# PIC32_Subsystem.net
KiCad netlist of a schematic drawn in Altium Designer
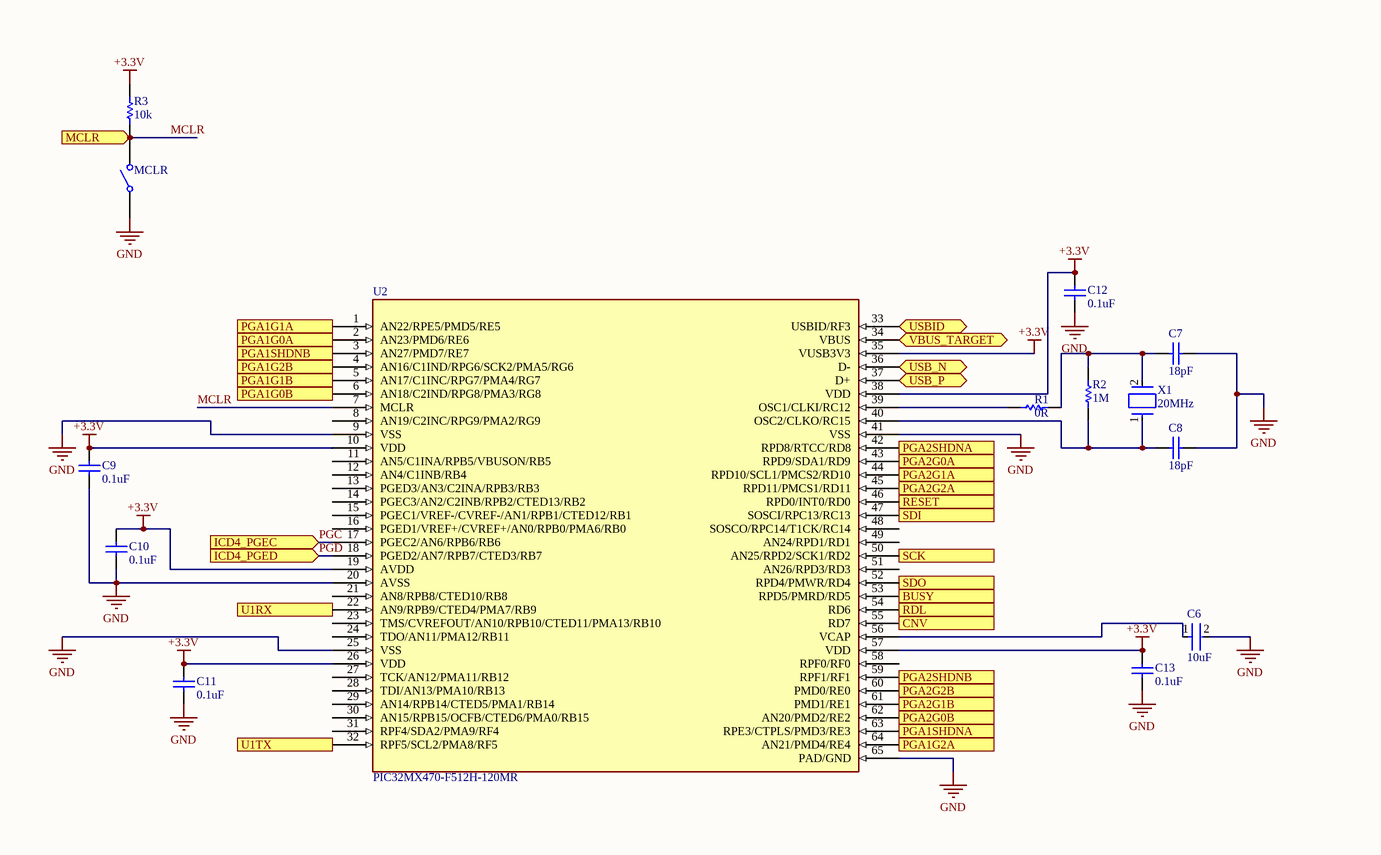
[diagram p0: PIC32_Subsystem.SchDoc, left]

(export (version "E")
  (design (tool "Eeschema 10.0.6"))
  (components
    (comp (ref "C6")
      (value "10uF")
      (footprint "FP-GRM188-0_1-e0_2_0_55-IPC_A")
      (fields (field (name "VOLTAGE") "6.3V") (field (name "TOLERANCE") "20%"))
      (libsource (lib "Altium Content Vault") (part "02cd4be3c70576c341d710602a673aa"))
    )
    (comp (ref "C7")
      (value "18pF")
      (footprint "CAPC1005X55X25LL05T10")
      (description "GRM1555C1H180GA01D")
      (fields (field (name "MANUFACTURER") "Murata"))
      (libsource (lib "Altium Content Vault") (part "CAP"))
    )
    (comp (ref "C8")
      (value "18pF")
      (footprint "CAPC1005X55X25LL05T10")
      (description "GRM1555C1H180GA01D")
      (fields (field (name "MANUFACTURER") "Murata"))
      (libsource (lib "Altium Content Vault") (part "CAP"))
    )
    (comp (ref "C9")
      (value "0.1uF")
      (footprint "CAPC1050X55X23ML05T13")
      (fields (field (name "MANUFACTURER") "Samsung Electro-Mechanics"))
      (libsource (lib "Altium Content Vault") (part "CAP-NP-2"))
    )
    (comp (ref "C10")
      (value "0.1uF")
      (footprint "CAPC1050X55X23ML05T13")
      (fields (field (name "MANUFACTURER") "Samsung Electro-Mechanics"))
      (libsource (lib "Altium Content Vault") (part "CAP-NP-2"))
    )
    (comp (ref "C11")
      (value "0.1uF")
      (footprint "CAPC1050X55X23ML05T13")
      (fields (field (name "MANUFACTURER") "Samsung Electro-Mechanics"))
      (libsource (lib "Altium Content Vault") (part "CAP-NP-2"))
    )
    (comp (ref "C12")
      (value "0.1uF")
      (footprint "CAPC1050X55X23ML05T13")
      (fields (field (name "MANUFACTURER") "Samsung Electro-Mechanics"))
      (libsource (lib "Altium Content Vault") (part "CAP-NP-2"))
    )
    (comp (ref "C13")
      (value "0.1uF")
      (footprint "CAPC1050X55X23ML05T13")
      (fields (field (name "MANUFACTURER") "Samsung Electro-Mechanics"))
      (libsource (lib "Altium Content Vault") (part "CAP-NP-2"))
    )
    (comp (ref "MCLR")
      (value "434121043816")
      (footprint "434121043816")
      (description "WS-TASV SMD Tact Switch 6.0X3.5 mm")
      (fields (field (name "MANUFACTURER") "Wuerth Elektronik"))
      (libsource (lib "Altium Content Vault") (part "WE-TACT-SW-2"))
    )
    (comp (ref "R1")
      (value "0R")
      (footprint "RESC1005X40X25NL05T10")
      (description "RC0402JR-070RL")
      (fields (field (name "MANUFACTURER") "Yageo / Phycomp"))
      (libsource (lib "Altium Content Vault") (part "RES"))
    )
    (comp (ref "R2")
      (value "1M")
      (footprint "RESC1005X40X25LL05T05")
      (fields
        (field (name "PARTNUMBER") "ERJ-2RKF1004X")
        (field (name "TOLERANCE") "1%")
        (field (name "MANUFACTURER") "Basic Passives")
      )
      (libsource (lib "Altium Content Vault") (part "RES-2"))
    )
    (comp (ref "R3")
      (value "10k")
      (footprint "RESC1005X40X25LL05T05")
      (fields (field (name "TOLERANCE") "1%") (field (name "MANUFACTURER") "Panasonic"))
      (libsource (lib "Altium Content Vault") (part "RES-2"))
    )
    (comp (ref "U2")
      (value "PIC32MX470-F512H-120MR")
      (footprint "QFN50P900X900X100-65N")
      (libsource (lib "PIC32MX470-F512H-120MR") (part "PIC32MX470-F512H-120MR"))
    )
    (comp (ref "X1")
      (value "20MHz")
      (footprint "FP-ABM7-MFG")
      (description "Crystal 20MHz ±20ppm 18pF SMD-2 6mm x 3.5mm\r\nABM7-20.000MHZ-D2Y-T")
      (fields (field (name "TOLERANCE") "20ppm"))
      (libsource (lib "Altium Content Vault") (part "c23a69dc6c9e2f18f2079038eb95dd1"))
    )
  )
  (nets
    (net (code "1") (name "+3.3V") (class "Default")
      (node (ref "C10") (pin "2") (pinfunction "2_2") (pintype "passive"))
      (node (ref "C11") (pin "2") (pinfunction "2_2") (pintype "passive"))
      (node (ref "C12") (pin "2") (pinfunction "2_2") (pintype "passive"))
      (node (ref "C13") (pin "2") (pinfunction "2_2") (pintype "passive"))
      (node (ref "C9") (pin "2") (pinfunction "2_2") (pintype "passive"))
      (node (ref "R3") (pin "2") (pinfunction "2_2") (pintype "passive"))
      (node (ref "U2") (pin "10") (pinfunction "VDD_10") (pintype "input"))
      (node (ref "U2") (pin "19") (pinfunction "AVDD_19") (pintype "input"))
      (node (ref "U2") (pin "26") (pinfunction "VDD_26") (pintype "input"))
      (node (ref "U2") (pin "35") (pinfunction "VUSB3V3_35") (pintype "input"))
      (node (ref "U2") (pin "38") (pinfunction "VDD_38") (pintype "input"))
      (node (ref "U2") (pin "57") (pinfunction "VDD_57") (pintype "input"))
    )
    (net (code "2") (name "/BUSY") (class "Default")
      (node (ref "U2") (pin "53") (pinfunction "RPD5/PMRD/RD5_53") (pintype "input"))
    )
    (net (code "3") (name "/CNV") (class "Default")
      (node (ref "U2") (pin "55") (pinfunction "RD7_55") (pintype "input"))
    )
    (net (code "4") (name "/MCLR") (class "Default")
      (node (ref "MCLR") (pin "2") (pinfunction "2_2") (pintype "passive"))
      (node (ref "R3") (pin "1") (pinfunction "1_1") (pintype "passive"))
      (node (ref "U2") (pin "7") (pinfunction "MCLR_7") (pintype "input"))
    )
    (net (code "5") (name "/PGA1G0A") (class "Default")
      (node (ref "U2") (pin "2") (pinfunction "AN23/PMD6/RE6_2") (pintype "input"))
    )
    (net (code "6") (name "/PGA1G0B") (class "Default")
      (node (ref "U2") (pin "6") (pinfunction "AN18/C2IND/RPG8/PMA3/RG8_6") (pintype "input"))
    )
    (net (code "7") (name "/PGA1G1A") (class "Default")
      (node (ref "U2") (pin "1") (pinfunction "AN22/RPE5/PMD5/RE5_1") (pintype "input"))
    )
    (net (code "8") (name "/PGA1G1B") (class "Default")
      (node (ref "U2") (pin "5") (pinfunction "AN17/C1INC/RPG7/PMA4/RG7_5") (pintype "input"))
    )
    (net (code "9") (name "/PGA1G2A") (class "Default")
      (node (ref "U2") (pin "64") (pinfunction "AN21/PMD4/RE4_64") (pintype "input"))
    )
    (net (code "10") (name "/PGA1G2B") (class "Default")
      (node (ref "U2") (pin "4") (pinfunction "AN16/C1IND/RPG6/SCK2/PMA5/RG6_4") (pintype "input"))
    )
    (net (code "11") (name "/PGA1SHDNA") (class "Default")
      (node (ref "U2") (pin "63") (pinfunction "RPE3/CTPLS/PMD3/RE3_63") (pintype "input"))
    )
    (net (code "12") (name "/PGA1SHDNB") (class "Default")
      (node (ref "U2") (pin "3") (pinfunction "AN27/PMD7/RE7_3") (pintype "input"))
    )
    (net (code "13") (name "/PGA2G0A") (class "Default")
      (node (ref "U2") (pin "43") (pinfunction "RPD9/SDA1/RD9_43") (pintype "input"))
    )
    (net (code "14") (name "/PGA2G0B") (class "Default")
      (node (ref "U2") (pin "62") (pinfunction "AN20/PMD2/RE2_62") (pintype "input"))
    )
    (net (code "15") (name "/PGA2G1A") (class "Default")
      (node (ref "U2") (pin "44") (pinfunction "RPD10/SCL1/PMCS2/RD10_44") (pintype "input"))
    )
    (net (code "16") (name "/PGA2G1B") (class "Default")
      (node (ref "U2") (pin "61") (pinfunction "PMD1/RE1_61") (pintype "input"))
    )
    (net (code "17") (name "/PGA2G2A") (class "Default")
      (node (ref "U2") (pin "45") (pinfunction "RPD11/PMCS1/RD11_45") (pintype "input"))
    )
    (net (code "18") (name "/PGA2G2B") (class "Default")
      (node (ref "U2") (pin "60") (pinfunction "PMD0/RE0_60") (pintype "input"))
    )
    (net (code "19") (name "/PGA2SHDNA") (class "Default")
      (node (ref "U2") (pin "42") (pinfunction "RPD8/RTCC/RD8_42") (pintype "input"))
    )
    (net (code "20") (name "/PGA2SHDNB") (class "Default")
      (node (ref "U2") (pin "59") (pinfunction "RPF1/RF1_59") (pintype "input"))
    )
    (net (code "21") (name "/PGC") (class "Default")
      (node (ref "U2") (pin "17") (pinfunction "PGEC2/AN6/RPB6/RB6_17") (pintype "input"))
    )
    (net (code "22") (name "/PGD") (class "Default")
      (node (ref "U2") (pin "18") (pinfunction "PGED2/AN7/RPB7/CTED3/RB7_18") (pintype "input"))
    )
    (net (code "23") (name "/RDL") (class "Default")
      (node (ref "U2") (pin "54") (pinfunction "RD6_54") (pintype "input"))
    )
    (net (code "24") (name "/RESET") (class "Default")
      (node (ref "U2") (pin "46") (pinfunction "RPD0/INT0/RD0_46") (pintype "input"))
    )
    (net (code "25") (name "/SCK") (class "Default")
      (node (ref "U2") (pin "50") (pinfunction "AN25/RPD2/SCK1/RD2_50") (pintype "input"))
    )
    (net (code "26") (name "/SDI") (class "Default")
      (node (ref "U2") (pin "47") (pinfunction "SOSCI/RPC13/RC13_47") (pintype "input"))
    )
    (net (code "27") (name "/SDO") (class "Default")
      (node (ref "U2") (pin "52") (pinfunction "RPD4/PMWR/RD4_52") (pintype "input"))
    )
    (net (code "28") (name "/U1RX") (class "Default")
      (node (ref "U2") (pin "22") (pinfunction "AN9/RPB9/CTED4/PMA7/RB9_22") (pintype "input"))
    )
    (net (code "29") (name "/U1TX") (class "Default")
      (node (ref "U2") (pin "32") (pinfunction "RPF5/SCL2/PMA8/RF5_32") (pintype "input"))
    )
    (net (code "30") (name "/USBID") (class "Default")
      (node (ref "U2") (pin "33") (pinfunction "USBID/RF3_33") (pintype "input"))
    )
    (net (code "31") (name "/USB_N") (class "Default")
      (node (ref "U2") (pin "36") (pinfunction "D-_36") (pintype "input"))
    )
    (net (code "32") (name "/USB_P") (class "Default")
      (node (ref "U2") (pin "37") (pinfunction "D+_37") (pintype "input"))
    )
    (net (code "33") (name "/VBUS_TARGET") (class "Default")
      (node (ref "U2") (pin "34") (pinfunction "VBUS_34") (pintype "input"))
    )
    (net (code "34") (name "GND") (class "Default")
      (node (ref "C10") (pin "1") (pinfunction "1_1") (pintype "passive"))
      (node (ref "C11") (pin "1") (pinfunction "1_1") (pintype "passive"))
      (node (ref "C12") (pin "1") (pinfunction "1_1") (pintype "passive"))
      (node (ref "C13") (pin "1") (pinfunction "1_1") (pintype "passive"))
      (node (ref "C6") (pin "2") (pinfunction "2_2") (pintype "passive"))
      (node (ref "C7") (pin "2") (pinfunction "2_2") (pintype "passive"))
      (node (ref "C8") (pin "2") (pinfunction "2_2") (pintype "passive"))
      (node (ref "C9") (pin "1") (pinfunction "1_1") (pintype "passive"))
      (node (ref "MCLR") (pin "1") (pinfunction "1_1") (pintype "passive"))
      (node (ref "U2") (pin "20") (pinfunction "AVSS_20") (pintype "input"))
      (node (ref "U2") (pin "25") (pinfunction "VSS_25") (pintype "input"))
      (node (ref "U2") (pin "41") (pinfunction "VSS_41") (pintype "input"))
      (node (ref "U2") (pin "65") (pinfunction "PAD/GND_65") (pintype "input"))
      (node (ref "U2") (pin "9") (pinfunction "VSS_9") (pintype "input"))
    )
    (net (code "35") (name "Net-(C7-Pad1)") (class "Default")
      (node (ref "C7") (pin "1") (pinfunction "1_1") (pintype "passive"))
      (node (ref "R1") (pin "2") (pinfunction "2_2") (pintype "passive"))
      (node (ref "R2") (pin "2") (pinfunction "2_2") (pintype "passive"))
      (node (ref "X1") (pin "2") (pinfunction "2_2") (pintype "passive"))
    )
    (net (code "36") (name "Net-(U2-OSC1{slash}CLKI{slash}RC12)") (class "Default")
      (node (ref "R1") (pin "1") (pinfunction "1_1") (pintype "passive"))
      (node (ref "U2") (pin "39") (pinfunction "OSC1/CLKI/RC12_39") (pintype "input"))
    )
    (net (code "37") (name "Net-(U2-OSC2{slash}CLKO{slash}RC15)") (class "Default")
      (node (ref "C8") (pin "1") (pinfunction "1_1") (pintype "passive"))
      (node (ref "R2") (pin "1") (pinfunction "1_1") (pintype "passive"))
      (node (ref "U2") (pin "40") (pinfunction "OSC2/CLKO/RC15_40") (pintype "input"))
      (node (ref "X1") (pin "1") (pinfunction "1_1") (pintype "passive"))
    )
    (net (code "38") (name "Net-(U2-VCAP)") (class "Default")
      (node (ref "C6") (pin "1") (pinfunction "1_1") (pintype "passive"))
      (node (ref "U2") (pin "56") (pinfunction "VCAP_56") (pintype "input"))
    )
    (net (code "39") (name "unconnected-(U2-AN4{slash}C1INB{slash}RB4-Pad12)") (class "Default")
      (node (ref "U2") (pin "12") (pinfunction "AN4/C1INB/RB4_12") (pintype "input"))
    )
    (net (code "40") (name "unconnected-(U2-AN5{slash}C1INA{slash}RPB5{slash}VBUSON{slash}RB5-Pad11)") (class "Default")
      (node (ref "U2") (pin "11") (pinfunction "AN5/C1INA/RPB5/VBUSON/RB5_11") (pintype "input"))
    )
    (net (code "41") (name "unconnected-(U2-AN8{slash}RPB8{slash}CTED10{slash}RB8-Pad21)") (class "Default")
      (node (ref "U2") (pin "21") (pinfunction "AN8/RPB8/CTED10/RB8_21") (pintype "input"))
    )
    (net (code "42") (name "unconnected-(U2-AN14{slash}RPB14{slash}CTED5{slash}PMA1{slash}RB14-Pad29)") (class "Default")
      (node (ref "U2") (pin "29") (pinfunction "AN14/RPB14/CTED5/PMA1/RB14_29") (pintype "input"))
    )
    (net (code "43") (name "unconnected-(U2-AN15{slash}RPB15{slash}OCFB{slash}CTED6{slash}PMA0{slash}RB15-Pad30)") (class "Default")
      (node (ref "U2") (pin "30") (pinfunction "AN15/RPB15/OCFB/CTED6/PMA0/RB15_30") (pintype "input"))
    )
    (net (code "44") (name "unconnected-(U2-AN19{slash}C2INC{slash}RPG9{slash}PMA2{slash}RG9-Pad8)") (class "Default")
      (node (ref "U2") (pin "8") (pinfunction "AN19/C2INC/RPG9/PMA2/RG9_8") (pintype "input"))
    )
    (net (code "45") (name "unconnected-(U2-AN24{slash}RPD1{slash}RD1-Pad49)") (class "Default")
      (node (ref "U2") (pin "49") (pinfunction "AN24/RPD1/RD1_49") (pintype "input"))
    )
    (net (code "46") (name "unconnected-(U2-AN26{slash}RPD3{slash}RD3-Pad51)") (class "Default")
      (node (ref "U2") (pin "51") (pinfunction "AN26/RPD3/RD3_51") (pintype "input"))
    )
    (net (code "47") (name "unconnected-(U2-PGEC1{slash}VREF-{slash}CVREF-{slash}AN1{slash}RPB1{slash}CTED12{slash}RB1-Pad15)") (class "Default")
      (node (ref "U2") (pin "15") (pinfunction "PGEC1/VREF-/CVREF-/AN1/RPB1/CTED12/RB1_15") (pintype "input"))
    )
    (net (code "48") (name "unconnected-(U2-PGEC3{slash}AN2{slash}C2INB{slash}RPB2{slash}CTED13{slash}RB2-Pad14)") (class "Default")
      (node (ref "U2") (pin "14") (pinfunction "PGEC3/AN2/C2INB/RPB2/CTED13/RB2_14") (pintype "input"))
    )
    (net (code "49") (name "unconnected-(U2-PGED1{slash}VREF+{slash}CVREF+{slash}AN0{slash}RPB0{slash}PMA6{slash}RB0-Pad16)") (class "Default")
      (node (ref "U2") (pin "16") (pinfunction "PGED1/VREF+/CVREF+/AN0/RPB0/PMA6/RB0_16") (pintype "input"))
    )
    (net (code "50") (name "unconnected-(U2-PGED3{slash}AN3{slash}C2INA{slash}RPB3{slash}RB3-Pad13)") (class "Default")
      (node (ref "U2") (pin "13") (pinfunction "PGED3/AN3/C2INA/RPB3/RB3_13") (pintype "input"))
    )
    (net (code "51") (name "unconnected-(U2-RPF0{slash}RF0-Pad58)") (class "Default")
      (node (ref "U2") (pin "58") (pinfunction "RPF0/RF0_58") (pintype "input"))
    )
    (net (code "52") (name "unconnected-(U2-RPF4{slash}SDA2{slash}PMA9{slash}RF4-Pad31)") (class "Default")
      (node (ref "U2") (pin "31") (pinfunction "RPF4/SDA2/PMA9/RF4_31") (pintype "input"))
    )
    (net (code "53") (name "unconnected-(U2-SOSCO{slash}RPC14{slash}T1CK{slash}RC14-Pad48)") (class "Default")
      (node (ref "U2") (pin "48") (pinfunction "SOSCO/RPC14/T1CK/RC14_48") (pintype "input"))
    )
    (net (code "54") (name "unconnected-(U2-TCK{slash}AN12{slash}PMA11{slash}RB12-Pad27)") (class "Default")
      (node (ref "U2") (pin "27") (pinfunction "TCK/AN12/PMA11/RB12_27") (pintype "input"))
    )
    (net (code "55") (name "unconnected-(U2-TDI{slash}AN13{slash}PMA10{slash}RB13-Pad28)") (class "Default")
      (node (ref "U2") (pin "28") (pinfunction "TDI/AN13/PMA10/RB13_28") (pintype "input"))
    )
    (net (code "56") (name "unconnected-(U2-TDO{slash}AN11{slash}PMA12{slash}RB11-Pad24)") (class "Default")
      (node (ref "U2") (pin "24") (pinfunction "TDO/AN11/PMA12/RB11_24") (pintype "input"))
    )
    (net (code "57") (name "unconnected-(U2-TMS{slash}CVREFOUT{slash}AN10{slash}RPB10{slash}CTED11{slash}PMA13{slash}RB10-Pad23)") (class "Default")
      (node (ref "U2") (pin "23") (pinfunction "TMS/CVREFOUT/AN10/RPB10/CTED11/PMA13/RB10_23") (pintype "input"))
    )
  )
)
